# PageTurner-Display.net
KiCad netlist of a schematic drawn in EAGLE
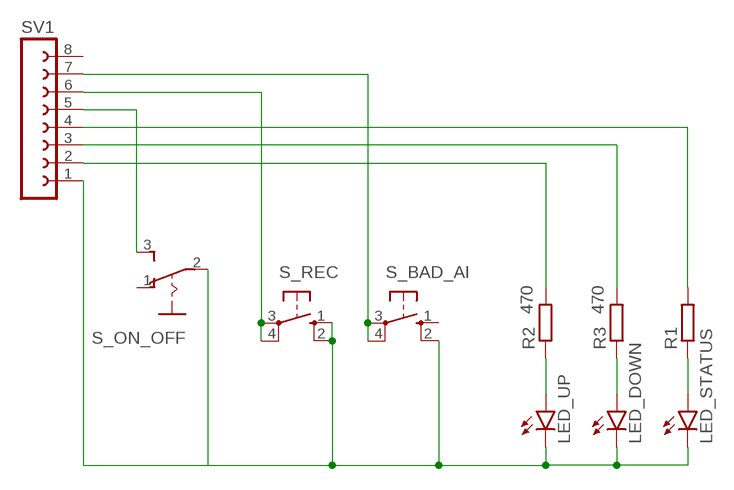
[diagram p0: schematic, sheet 1]

(export (version "E")
  (design (tool "Eeschema 10.0.6"))
  (components
    (comp (ref "LED_DOWN")
      (value "LED3MM")
      (footprint "eagle-import:LED3MM")
      (libsource (lib "eagle-import") (part "LED3MM"))
    )
    (comp (ref "LED_STATUS")
      (value "LED3MM")
      (footprint "eagle-import:LED3MM")
      (libsource (lib "eagle-import") (part "LED3MM"))
    )
    (comp (ref "LED_UP")
      (value "LED3MM")
      (footprint "eagle-import:LED3MM")
      (libsource (lib "eagle-import") (part "LED3MM"))
    )
    (comp (ref "R1")
      (value "470")
      (footprint "eagle-import:0207_12")
      (libsource (lib "eagle-import") (part "R-EU_0207/12"))
    )
    (comp (ref "R2")
      (value "470")
      (footprint "eagle-import:0207_12")
      (libsource (lib "eagle-import") (part "R-EU_0207/12"))
    )
    (comp (ref "R3")
      (value "470")
      (footprint "eagle-import:0207_12")
      (libsource (lib "eagle-import") (part "R-EU_0207/12"))
    )
    (comp (ref "SV1")
      (value "FE08-1")
      (footprint "eagle-import:FE08")
      (libsource (lib "eagle-import") (part "FE08-1"))
    )
    (comp (ref "S_BAD_AI")
      (value "10-XX")
      (footprint "eagle-import:B3F-10XX")
      (fields (field (name "MPN") "B3F-1000"))
      (libsource (lib "eagle-import") (part "10-XX"))
    )
    (comp (ref "S_ON_OFF")
      (value "255SB")
      (footprint "eagle-import:255SB")
      (libsource (lib "eagle-import") (part "255SB"))
    )
    (comp (ref "S_REC")
      (value "10-XX")
      (footprint "eagle-import:B3F-10XX")
      (fields (field (name "MPN") "B3F-1000"))
      (libsource (lib "eagle-import") (part "10-XX"))
    )
  )
  (nets
    (net (code "1") (name "Net-(LED_DOWN-C)") (class "Default")
      (node (ref "LED_DOWN") (pin "K") (pinfunction "C_K") (pintype "passive"))
      (node (ref "LED_STATUS") (pin "K") (pinfunction "C_K") (pintype "passive"))
      (node (ref "LED_UP") (pin "K") (pinfunction "C_K") (pintype "passive"))
      (node (ref "SV1") (pin "1") (pinfunction "1_1") (pintype "passive"))
      (node (ref "S_BAD_AI") (pin "2") (pinfunction "S1_2") (pintype "passive"))
      (node (ref "S_ON_OFF") (pin "2") (pinfunction "P_2") (pintype "passive"))
      (node (ref "S_REC") (pin "1") (pinfunction "S_1") (pintype "passive"))
      (node (ref "S_REC") (pin "2") (pinfunction "S1_2") (pintype "passive"))
    )
    (net (code "2") (name "Net-(LED_DOWN-PadA)") (class "Default")
      (node (ref "LED_DOWN") (pin "A") (pinfunction "A_A") (pintype "passive"))
      (node (ref "R3") (pin "1") (pinfunction "1_1") (pintype "passive"))
    )
    (net (code "3") (name "Net-(LED_STATUS-PadA)") (class "Default")
      (node (ref "LED_STATUS") (pin "A") (pinfunction "A_A") (pintype "passive"))
      (node (ref "R1") (pin "1") (pinfunction "1_1") (pintype "passive"))
    )
    (net (code "4") (name "Net-(LED_UP-PadA)") (class "Default")
      (node (ref "LED_UP") (pin "A") (pinfunction "A_A") (pintype "passive"))
      (node (ref "R2") (pin "1") (pinfunction "1_1") (pintype "passive"))
    )
    (net (code "5") (name "Net-(R1-Pad2)") (class "Default")
      (node (ref "R1") (pin "2") (pinfunction "2_2") (pintype "passive"))
      (node (ref "SV1") (pin "4") (pinfunction "4_4") (pintype "passive"))
    )
    (net (code "6") (name "Net-(R2-Pad2)") (class "Default")
      (node (ref "R2") (pin "2") (pinfunction "2_2") (pintype "passive"))
      (node (ref "SV1") (pin "2") (pinfunction "2_2") (pintype "passive"))
    )
    (net (code "7") (name "Net-(R3-Pad2)") (class "Default")
      (node (ref "R3") (pin "2") (pinfunction "2_2") (pintype "passive"))
      (node (ref "SV1") (pin "3") (pinfunction "3_3") (pintype "passive"))
    )
    (net (code "8") (name "Net-(S_BAD_AI-P)") (class "Default")
      (node (ref "SV1") (pin "7") (pinfunction "7_7") (pintype "passive"))
      (node (ref "S_BAD_AI") (pin "3") (pinfunction "P_3") (pintype "passive"))
      (node (ref "S_BAD_AI") (pin "4") (pinfunction "P1_4") (pintype "passive"))
    )
    (net (code "9") (name "Net-(S_ON_OFF-S)") (class "Default")
      (node (ref "SV1") (pin "5") (pinfunction "5_5") (pintype "passive"))
      (node (ref "S_ON_OFF") (pin "3") (pinfunction "S_3") (pintype "passive"))
    )
    (net (code "10") (name "Net-(S_REC-P)") (class "Default")
      (node (ref "SV1") (pin "6") (pinfunction "6_6") (pintype "passive"))
      (node (ref "S_REC") (pin "3") (pinfunction "P_3") (pintype "passive"))
      (node (ref "S_REC") (pin "4") (pinfunction "P1_4") (pintype "passive"))
    )
    (net (code "11") (name "unconnected-(SV1-Pad8)") (class "Default")
      (node (ref "SV1") (pin "8") (pinfunction "8_8") (pintype "passive"))
    )
    (net (code "12") (name "unconnected-(S_BAD_AI-S-Pad1)") (class "Default")
      (node (ref "S_BAD_AI") (pin "1") (pinfunction "S_1") (pintype "passive"))
    )
    (net (code "13") (name "unconnected-(S_ON_OFF-O-Pad1)") (class "Default")
      (node (ref "S_ON_OFF") (pin "1") (pinfunction "O_1") (pintype "passive"))
    )
  )
)
